# Mainsnode_v2.net
KiCad netlist of a schematic drawn in EAGLE
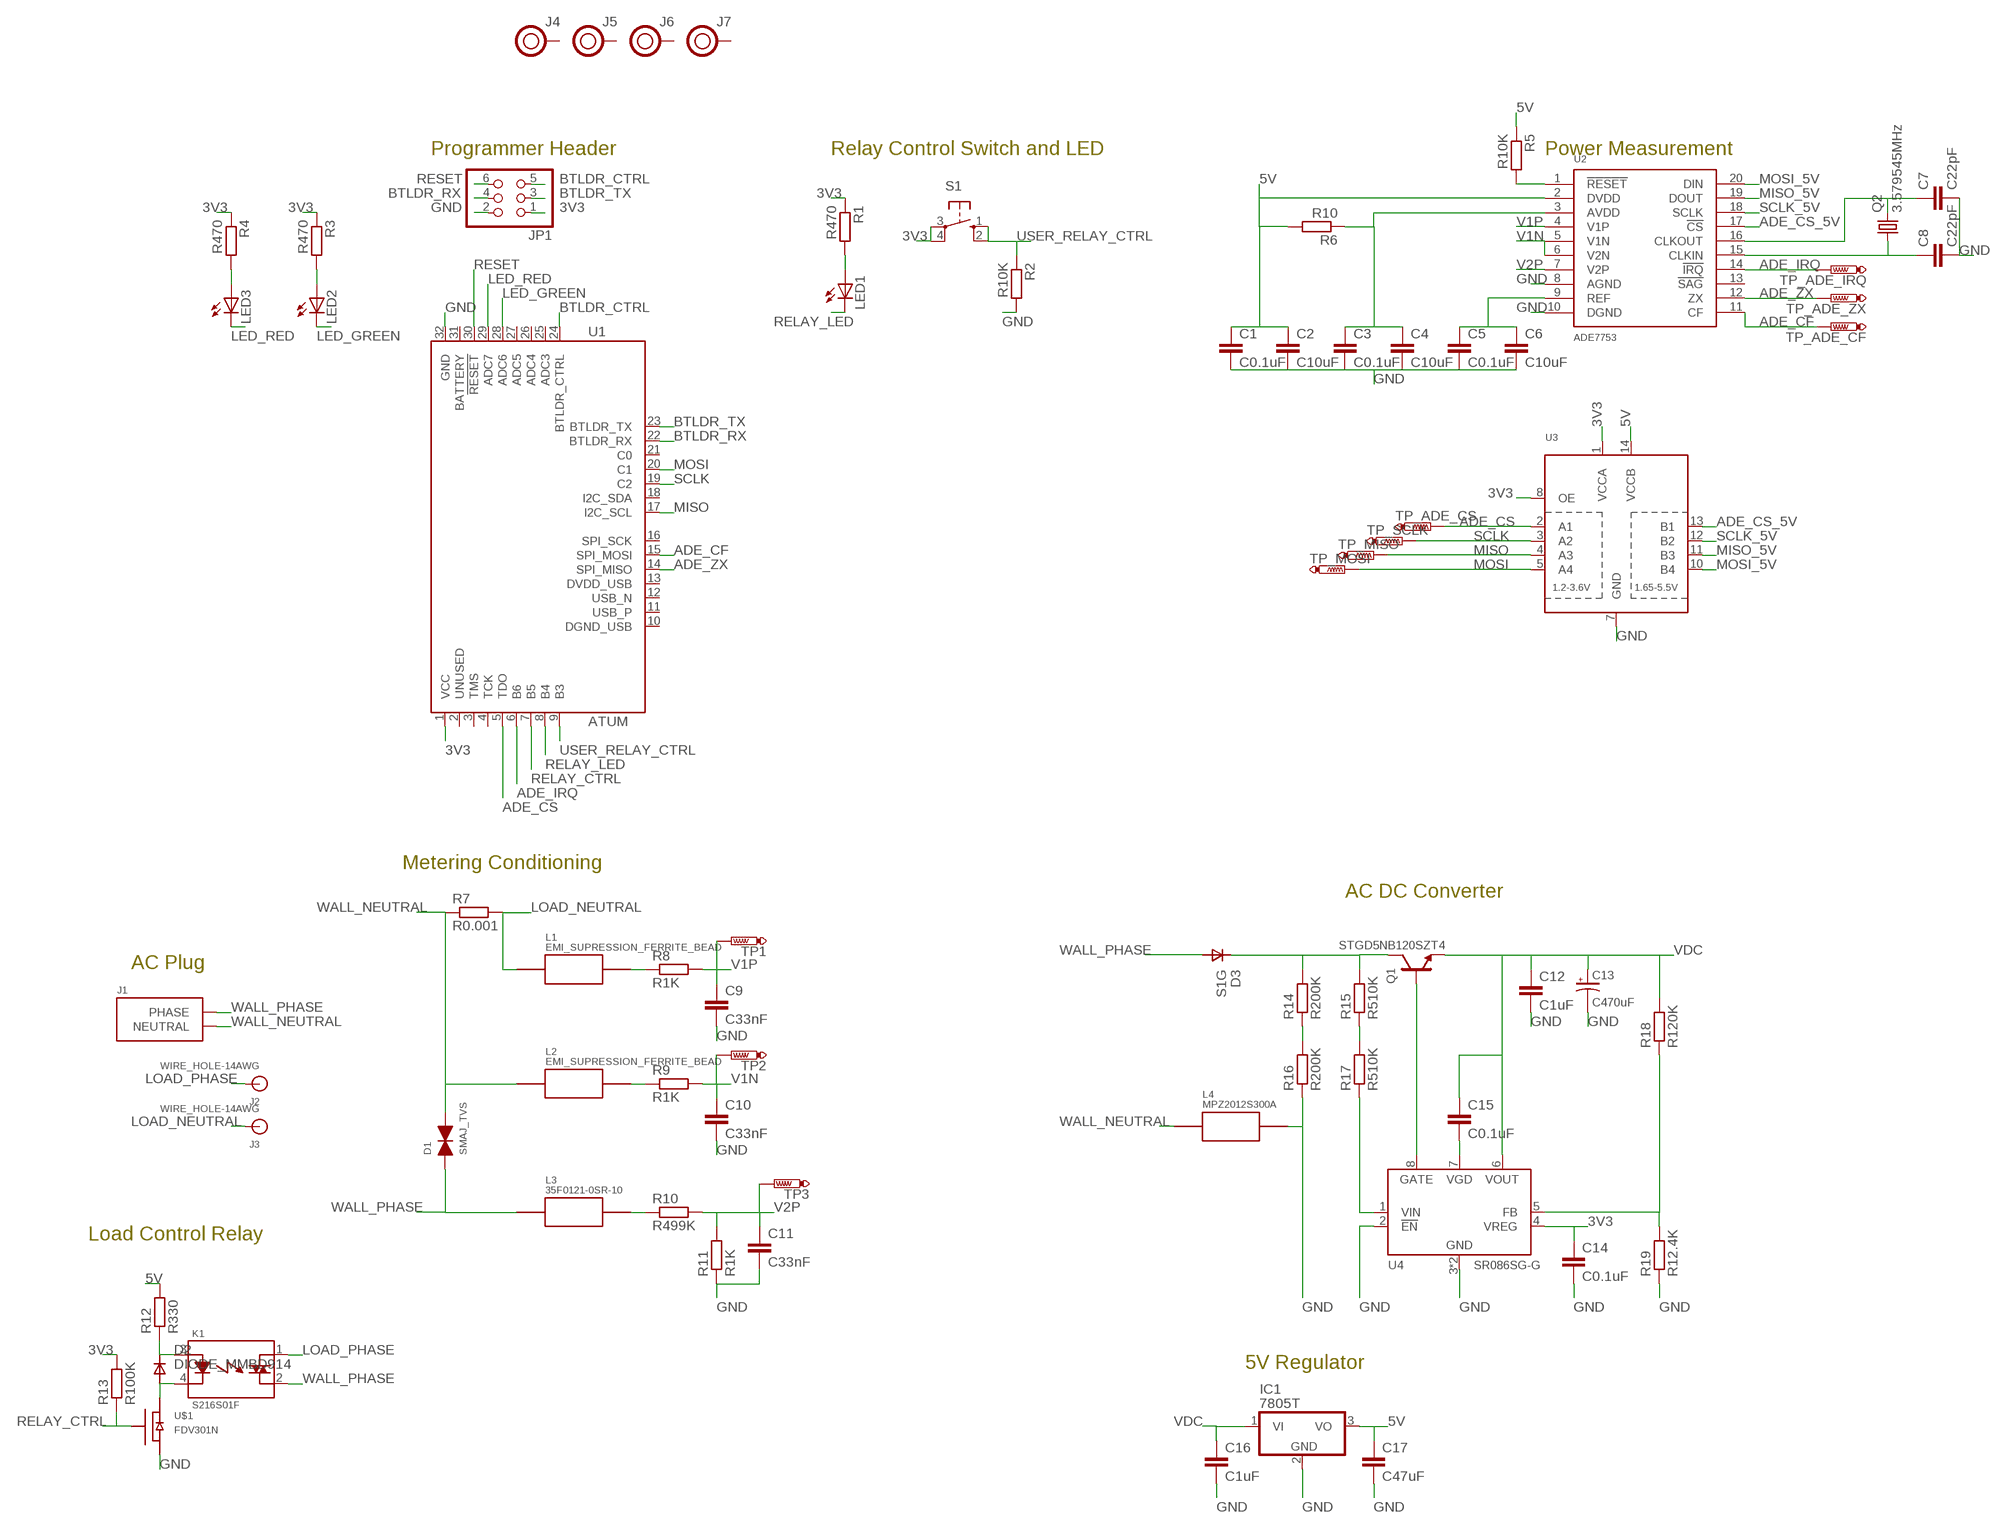
[diagram p0: schematic, sheet 1]

(export (version "E")
  (design (tool "Eeschema 10.0.6"))
  (components
    (comp (ref "C1")
      (value "C0.1uF")
      (footprint "eagle-import:C0805")
      (libsource (lib "eagle-import") (part "C-EUC0805"))
    )
    (comp (ref "C2")
      (value "C10uF")
      (footprint "eagle-import:C0805")
      (libsource (lib "eagle-import") (part "C-EUC0805"))
    )
    (comp (ref "C3")
      (value "C0.1uF")
      (footprint "eagle-import:C0805")
      (libsource (lib "eagle-import") (part "C-EUC0805"))
    )
    (comp (ref "C4")
      (value "C10uF")
      (footprint "eagle-import:C0805")
      (libsource (lib "eagle-import") (part "C-EUC0805"))
    )
    (comp (ref "C5")
      (value "C0.1uF")
      (footprint "eagle-import:C0805")
      (libsource (lib "eagle-import") (part "C-EUC0805"))
    )
    (comp (ref "C6")
      (value "C10uF")
      (footprint "eagle-import:C0805")
      (libsource (lib "eagle-import") (part "C-EUC0805"))
    )
    (comp (ref "C7")
      (value "C22pF")
      (footprint "eagle-import:C0805")
      (libsource (lib "eagle-import") (part "C-EUC0805"))
    )
    (comp (ref "C8")
      (value "C22pF")
      (footprint "eagle-import:C0805")
      (libsource (lib "eagle-import") (part "C-EUC0805"))
    )
    (comp (ref "C9")
      (value "C33nF")
      (footprint "eagle-import:C0805")
      (libsource (lib "eagle-import") (part "C-EUC0805"))
    )
    (comp (ref "C10")
      (value "C33nF")
      (footprint "eagle-import:C0805")
      (libsource (lib "eagle-import") (part "C-EUC0805"))
    )
    (comp (ref "C11")
      (value "C33nF")
      (footprint "eagle-import:C0805")
      (libsource (lib "eagle-import") (part "C-EUC0805"))
    )
    (comp (ref "C12")
      (value "C1uF")
      (footprint "eagle-import:C0805")
      (libsource (lib "eagle-import") (part "C-EUC0805"))
    )
    (comp (ref "C13")
      (value "C470uF")
      (footprint "eagle-import:CAP_SM_10MM")
      (libsource (lib "eagle-import") (part "CAP_EEE-FP1E471AP"))
    )
    (comp (ref "C14")
      (value "C0.1uF")
      (footprint "eagle-import:C0805")
      (libsource (lib "eagle-import") (part "C-EUC0805"))
    )
    (comp (ref "C15")
      (value "C0.1uF")
      (footprint "eagle-import:C0805")
      (libsource (lib "eagle-import") (part "C-EUC0805"))
    )
    (comp (ref "C16")
      (value "C1uF")
      (footprint "eagle-import:C0805")
      (libsource (lib "eagle-import") (part "C-EUC0805"))
    )
    (comp (ref "C17")
      (value "C47uF")
      (footprint "eagle-import:C0805")
      (libsource (lib "eagle-import") (part "C-EUC0805"))
    )
    (comp (ref "D1")
      (value "SMAJ_TVS")
      (footprint "eagle-import:DO214_TVS")
      (libsource (lib "eagle-import") (part "SMAJ_TVS"))
    )
    (comp (ref "D2")
      (value "DIODE_MMBD914")
      (footprint "eagle-import:SOT-23")
      (libsource (lib "eagle-import") (part "DIODE_MMBD914"))
    )
    (comp (ref "D3")
      (value "S1G")
      (footprint "eagle-import:DO-214AC")
      (libsource (lib "eagle-import") (part "S1G"))
    )
    (comp (ref "IC1")
      (value "7805T")
      (footprint "eagle-import:TO220H")
      (libsource (lib "eagle-import") (part "78T05"))
    )
    (comp (ref "J1")
      (value "AC-PLUG-2")
      (footprint "eagle-import:AC_MALE_PINS_2")
      (libsource (lib "eagle-import") (part "AC-PLUG-2"))
    )
    (comp (ref "J2")
      (value "WIRE_HOLE-14AWG")
      (footprint "eagle-import:WIRE_HOLE-14AWG")
      (libsource (lib "eagle-import") (part "WIRE_HOLE-14AWG"))
    )
    (comp (ref "J3")
      (value "WIRE_HOLE-14AWG")
      (footprint "eagle-import:WIRE_HOLE-14AWG")
      (libsource (lib "eagle-import") (part "WIRE_HOLE-14AWG"))
    )
    (comp (ref "J4")
      (value "HOLE")
      (footprint "eagle-import:HOLE-0.125")
      (libsource (lib "eagle-import") (part "HOLE"))
    )
    (comp (ref "J5")
      (value "HOLE")
      (footprint "eagle-import:HOLE-0.125")
      (libsource (lib "eagle-import") (part "HOLE"))
    )
    (comp (ref "J6")
      (value "HOLE")
      (footprint "eagle-import:HOLE-0.125")
      (libsource (lib "eagle-import") (part "HOLE"))
    )
    (comp (ref "J7")
      (value "HOLE")
      (footprint "eagle-import:HOLE-0.125")
      (libsource (lib "eagle-import") (part "HOLE"))
    )
    (comp (ref "JP1")
      (value "PINHD-2X3")
      (footprint "eagle-import:2X03")
      (libsource (lib "eagle-import") (part "PINHD-2X3"))
    )
    (comp (ref "K1")
      (value "S216S01F")
      (footprint "eagle-import:RELAY_SX16S0X")
      (libsource (lib "eagle-import") (part "S216S01F"))
    )
    (comp (ref "L1")
      (value "EMI_SUPRESSION_FERRITE_BEAD")
      (footprint "eagle-import:L1806")
      (libsource (lib "eagle-import") (part "EMI_SUPRESSION_FERRITE_BEAD"))
    )
    (comp (ref "L2")
      (value "EMI_SUPRESSION_FERRITE_BEAD")
      (footprint "eagle-import:L1806")
      (fields (field (name "DIGIKEY") "240-2418-1-ND"))
      (libsource (lib "eagle-import") (part "EMI_SUPRESSION_FERRITE_BEAD"))
    )
    (comp (ref "L3")
      (value "35F0121-0SR-10")
      (footprint "eagle-import:35F0102")
      (libsource (lib "eagle-import") (part "35F0121-0SR-10"))
    )
    (comp (ref "L4")
      (value "MPZ2012S300A")
      (footprint "eagle-import:0805_RESISTOR")
      (libsource (lib "eagle-import") (part "MPZ2012S300A"))
    )
    (comp (ref "LED1")
      (value "LEDCHIP-LED0805")
      (footprint "eagle-import:CHIP-LED0805")
      (libsource (lib "eagle-import") (part "LEDCHIP-LED0805"))
    )
    (comp (ref "LED2")
      (value "LEDCHIP-LED0805")
      (footprint "eagle-import:CHIP-LED0805")
      (libsource (lib "eagle-import") (part "LEDCHIP-LED0805"))
    )
    (comp (ref "LED3")
      (value "LEDCHIP-LED0805")
      (footprint "eagle-import:CHIP-LED0805")
      (libsource (lib "eagle-import") (part "LEDCHIP-LED0805"))
    )
    (comp (ref "Q1")
      (value "STGD5NB120SZT4")
      (footprint "eagle-import:DPAK")
      (libsource (lib "eagle-import") (part "STGD5NB120SZT4"))
    )
    (comp (ref "Q2")
      (value "3.579545MHz")
      (footprint "eagle-import:HC49_S")
      (libsource (lib "eagle-import") (part "CRYSTALHC49S"))
    )
    (comp (ref "R1")
      (value "R470")
      (footprint "eagle-import:R0805")
      (libsource (lib "eagle-import") (part "R-EU_R0805"))
    )
    (comp (ref "R2")
      (value "R10K")
      (footprint "eagle-import:R0805")
      (libsource (lib "eagle-import") (part "R-EU_R0805"))
    )
    (comp (ref "R3")
      (value "R470")
      (footprint "eagle-import:R0805")
      (libsource (lib "eagle-import") (part "R-EU_R0805"))
    )
    (comp (ref "R4")
      (value "R470")
      (footprint "eagle-import:R0805")
      (libsource (lib "eagle-import") (part "R-EU_R0805"))
    )
    (comp (ref "R5")
      (value "R10K")
      (footprint "eagle-import:R0805")
      (libsource (lib "eagle-import") (part "R-EU_R0805"))
    )
    (comp (ref "R6")
      (value "R10")
      (footprint "eagle-import:R0805")
      (libsource (lib "eagle-import") (part "R-EU_R0805"))
    )
    (comp (ref "R7")
      (value "R0.001")
      (footprint "eagle-import:R2512")
      (libsource (lib "eagle-import") (part "R-EU_R2512"))
    )
    (comp (ref "R8")
      (value "R1K")
      (footprint "eagle-import:R0805")
      (libsource (lib "eagle-import") (part "R-EU_R0805"))
    )
    (comp (ref "R9")
      (value "R1K")
      (footprint "eagle-import:R0805")
      (libsource (lib "eagle-import") (part "R-EU_R0805"))
    )
    (comp (ref "R10")
      (value "R499K")
      (footprint "eagle-import:R0805")
      (libsource (lib "eagle-import") (part "R-EU_R0805"))
    )
    (comp (ref "R11")
      (value "R1K")
      (footprint "eagle-import:R0805")
      (libsource (lib "eagle-import") (part "R-EU_R0805"))
    )
    (comp (ref "R12")
      (value "R330")
      (footprint "eagle-import:R0805")
      (libsource (lib "eagle-import") (part "R-EU_R0805"))
    )
    (comp (ref "R13")
      (value "R100K")
      (footprint "eagle-import:R0805")
      (libsource (lib "eagle-import") (part "R-EU_R0805"))
    )
    (comp (ref "R14")
      (value "R200K")
      (footprint "eagle-import:R0805")
      (libsource (lib "eagle-import") (part "R-EU_R0805"))
    )
    (comp (ref "R15")
      (value "R510K")
      (footprint "eagle-import:R0805")
      (libsource (lib "eagle-import") (part "R-EU_R0805"))
    )
    (comp (ref "R16")
      (value "R200K")
      (footprint "eagle-import:R0805")
      (libsource (lib "eagle-import") (part "R-EU_R0805"))
    )
    (comp (ref "R17")
      (value "R510K")
      (footprint "eagle-import:R0805")
      (libsource (lib "eagle-import") (part "R-EU_R0805"))
    )
    (comp (ref "R18")
      (value "R120K")
      (footprint "eagle-import:R0805")
      (libsource (lib "eagle-import") (part "R-EU_R0805"))
    )
    (comp (ref "R19")
      (value "R12.4K")
      (footprint "eagle-import:R0805")
      (libsource (lib "eagle-import") (part "R-EU_R0805"))
    )
    (comp (ref "S1")
      (value "10-XX")
      (footprint "eagle-import:B3F-10XX")
      (fields (field (name "MPN") "B3F-1000"))
      (libsource (lib "eagle-import") (part "10-XX"))
    )
    (comp (ref "TP1")
      (value "PTR1PAD1-13")
      (footprint "eagle-import:P1-13")
      (libsource (lib "eagle-import") (part "PTR1PAD1-13"))
    )
    (comp (ref "TP2")
      (value "PTR1PAD1-13")
      (footprint "eagle-import:P1-13")
      (libsource (lib "eagle-import") (part "PTR1PAD1-13"))
    )
    (comp (ref "TP3")
      (value "PTR1PAD1-13")
      (footprint "eagle-import:P1-13")
      (libsource (lib "eagle-import") (part "PTR1PAD1-13"))
    )
    (comp (ref "TP_ADE_CF")
      (value "PTR1PAD1-13")
      (footprint "eagle-import:P1-13")
      (libsource (lib "eagle-import") (part "PTR1PAD1-13"))
    )
    (comp (ref "TP_ADE_CS")
      (value "PTR1PAD1-13")
      (footprint "eagle-import:P1-13")
      (libsource (lib "eagle-import") (part "PTR1PAD1-13"))
    )
    (comp (ref "TP_ADE_IRQ")
      (value "PTR1PAD1-13")
      (footprint "eagle-import:P1-13")
      (libsource (lib "eagle-import") (part "PTR1PAD1-13"))
    )
    (comp (ref "TP_ADE_ZX")
      (value "PTR1PAD1-13")
      (footprint "eagle-import:P1-13")
      (libsource (lib "eagle-import") (part "PTR1PAD1-13"))
    )
    (comp (ref "TP_MISO")
      (value "PTR1PAD1-13")
      (footprint "eagle-import:P1-13")
      (libsource (lib "eagle-import") (part "PTR1PAD1-13"))
    )
    (comp (ref "TP_MOSI")
      (value "PTR1PAD1-13")
      (footprint "eagle-import:P1-13")
      (libsource (lib "eagle-import") (part "PTR1PAD1-13"))
    )
    (comp (ref "TP_SCLK")
      (value "PTR1PAD1-13")
      (footprint "eagle-import:P1-13")
      (libsource (lib "eagle-import") (part "PTR1PAD1-13"))
    )
    (comp (ref "U$1")
      (value "FDV301N")
      (footprint "eagle-import:SOT-23")
      (libsource (lib "eagle-import") (part "FDV301N"))
    )
    (comp (ref "U1")
      (value "ATUM")
      (footprint "eagle-import:ATUM")
      (libsource (lib "eagle-import") (part "ATUM"))
    )
    (comp (ref "U2")
      (value "ADE7753")
      (footprint "eagle-import:SSOP-20")
      (libsource (lib "eagle-import") (part "ADE7753"))
    )
    (comp (ref "U3")
      (value "TXB0104PWR")
      (footprint "eagle-import:TSSOP14")
      (libsource (lib "eagle-import") (part "TXB0104PWR"))
    )
    (comp (ref "U4")
      (value "SR086SG-G")
      (footprint "eagle-import:SR086")
      (libsource (lib "eagle-import") (part "SR086SG-G"))
    )
  )
  (nets
    (net (code "1") (name "/3V3") (class "Default")
      (node (ref "C14") (pin "1") (pinfunction "1_1") (pintype "passive"))
      (node (ref "JP1") (pin "1") (pinfunction "1_1") (pintype "passive"))
      (node (ref "R1") (pin "1") (pinfunction "1_1") (pintype "passive"))
      (node (ref "R13") (pin "2") (pinfunction "2_2") (pintype "passive"))
      (node (ref "R3") (pin "1") (pinfunction "1_1") (pintype "passive"))
      (node (ref "R4") (pin "1") (pinfunction "1_1") (pintype "passive"))
      (node (ref "S1") (pin "3") (pinfunction "P_3") (pintype "passive"))
      (node (ref "S1") (pin "4") (pinfunction "P1_4") (pintype "passive"))
      (node (ref "U1") (pin "1") (pinfunction "VCC_1") (pintype "bidirectional"))
      (node (ref "U3") (pin "1") (pinfunction "VCCA_1") (pintype "bidirectional"))
      (node (ref "U3") (pin "8") (pinfunction "OE_8") (pintype "bidirectional"))
      (node (ref "U4") (pin "4") (pinfunction "VREG_4") (pintype "bidirectional"))
    )
    (net (code "2") (name "/5V") (class "Default")
      (node (ref "C1") (pin "1") (pinfunction "1_1") (pintype "passive"))
      (node (ref "C17") (pin "1") (pinfunction "1_1") (pintype "passive"))
      (node (ref "C2") (pin "1") (pinfunction "1_1") (pintype "passive"))
      (node (ref "IC1") (pin "3") (pinfunction "VO_3") (pintype "passive"))
      (node (ref "R12") (pin "2") (pinfunction "2_2") (pintype "passive"))
      (node (ref "R5") (pin "1") (pinfunction "1_1") (pintype "passive"))
      (node (ref "R6") (pin "2") (pinfunction "2_2") (pintype "passive"))
      (node (ref "U2") (pin "2") (pinfunction "DVDD_2") (pintype "bidirectional"))
      (node (ref "U3") (pin "14") (pinfunction "VCCB_14") (pintype "bidirectional"))
    )
    (net (code "3") (name "/ADE_CF") (class "Default")
      (node (ref "TP_ADE_CF") (pin "TP") (pinfunction "TP_TP") (pintype "input"))
      (node (ref "U1") (pin "15") (pinfunction "SPI_MOSI_15") (pintype "bidirectional"))
      (node (ref "U2") (pin "11") (pinfunction "CF_11") (pintype "bidirectional"))
    )
    (net (code "4") (name "/ADE_CS") (class "Default")
      (node (ref "TP_ADE_CS") (pin "TP") (pinfunction "TP_TP") (pintype "input"))
      (node (ref "U1") (pin "5") (pinfunction "TDO_5") (pintype "bidirectional"))
      (node (ref "U3") (pin "2") (pinfunction "A1_2") (pintype "bidirectional"))
    )
    (net (code "5") (name "/ADE_CS_5V") (class "Default")
      (node (ref "U2") (pin "17") (pinfunction "~{CS}_17") (pintype "bidirectional"))
      (node (ref "U3") (pin "13") (pinfunction "B1_13") (pintype "bidirectional"))
    )
    (net (code "6") (name "/ADE_IRQ") (class "Default")
      (node (ref "TP_ADE_IRQ") (pin "TP") (pinfunction "TP_TP") (pintype "input"))
      (node (ref "U1") (pin "6") (pinfunction "B6_6") (pintype "bidirectional"))
      (node (ref "U2") (pin "14") (pinfunction "~{IRQ}_14") (pintype "bidirectional"))
    )
    (net (code "7") (name "/ADE_ZX") (class "Default")
      (node (ref "TP_ADE_ZX") (pin "TP") (pinfunction "TP_TP") (pintype "input"))
      (node (ref "U1") (pin "14") (pinfunction "SPI_MISO_14") (pintype "bidirectional"))
      (node (ref "U2") (pin "12") (pinfunction "ZX_12") (pintype "bidirectional"))
    )
    (net (code "8") (name "/BTLDR_CTRL") (class "Default")
      (node (ref "JP1") (pin "5") (pinfunction "5_5") (pintype "passive"))
      (node (ref "U1") (pin "24") (pinfunction "BTLDR_CTRL_24") (pintype "bidirectional"))
    )
    (net (code "9") (name "/BTLDR_RX") (class "Default")
      (node (ref "JP1") (pin "4") (pinfunction "4_4") (pintype "passive"))
      (node (ref "U1") (pin "22") (pinfunction "BTLDR_RX_22") (pintype "bidirectional"))
    )
    (net (code "10") (name "/BTLDR_TX") (class "Default")
      (node (ref "JP1") (pin "3") (pinfunction "3_3") (pintype "passive"))
      (node (ref "U1") (pin "23") (pinfunction "BTLDR_TX_23") (pintype "bidirectional"))
    )
    (net (code "11") (name "/GND") (class "Default")
      (node (ref "C1") (pin "2") (pinfunction "2_2") (pintype "passive"))
      (node (ref "C10") (pin "2") (pinfunction "2_2") (pintype "passive"))
      (node (ref "C11") (pin "2") (pinfunction "2_2") (pintype "passive"))
      (node (ref "C12") (pin "2") (pinfunction "2_2") (pintype "passive"))
      (node (ref "C13") (pin "-") (pinfunction "-_-") (pintype "bidirectional"))
      (node (ref "C14") (pin "2") (pinfunction "2_2") (pintype "passive"))
      (node (ref "C16") (pin "2") (pinfunction "2_2") (pintype "passive"))
      (node (ref "C17") (pin "2") (pinfunction "2_2") (pintype "passive"))
      (node (ref "C2") (pin "2") (pinfunction "2_2") (pintype "passive"))
      (node (ref "C3") (pin "2") (pinfunction "2_2") (pintype "passive"))
      (node (ref "C4") (pin "2") (pinfunction "2_2") (pintype "passive"))
      (node (ref "C5") (pin "2") (pinfunction "2_2") (pintype "passive"))
      (node (ref "C6") (pin "2") (pinfunction "2_2") (pintype "passive"))
      (node (ref "C7") (pin "2") (pinfunction "2_2") (pintype "passive"))
      (node (ref "C8") (pin "2") (pinfunction "2_2") (pintype "passive"))
      (node (ref "C9") (pin "2") (pinfunction "2_2") (pintype "passive"))
      (node (ref "IC1") (pin "2") (pinfunction "GND_2") (pintype "passive"))
      (node (ref "JP1") (pin "2") (pinfunction "2_2") (pintype "passive"))
      (node (ref "L4") (pin "P$2") (pinfunction "P$2_P$2") (pintype "bidirectional"))
      (node (ref "R11") (pin "1") (pinfunction "1_1") (pintype "passive"))
      (node (ref "R16") (pin "1") (pinfunction "1_1") (pintype "passive"))
      (node (ref "R19") (pin "1") (pinfunction "1_1") (pintype "passive"))
      (node (ref "R2") (pin "2") (pinfunction "2_2") (pintype "passive"))
      (node (ref "U$1") (pin "2") (pinfunction "S_2") (pintype "bidirectional"))
      (node (ref "U1") (pin "32") (pinfunction "GND_32") (pintype "bidirectional"))
      (node (ref "U2") (pin "10") (pinfunction "DGND_10") (pintype "bidirectional"))
      (node (ref "U2") (pin "8") (pinfunction "AGND_8") (pintype "bidirectional"))
      (node (ref "U3") (pin "7") (pinfunction "GND_7") (pintype "bidirectional"))
      (node (ref "U4") (pin "2") (pinfunction "~{EN}_2") (pintype "bidirectional"))
      (node (ref "U4") (pin "3") (pinfunction "GND_3") (pintype "bidirectional"))
      (node (ref "U4") (pin "PAD") (pinfunction "GND_PAD") (pintype "bidirectional"))
    )
    (net (code "12") (name "/LED_GREEN") (class "Default")
      (node (ref "LED2") (pin "C") (pinfunction "C_C") (pintype "passive"))
      (node (ref "U1") (pin "28") (pinfunction "ADC6_28") (pintype "bidirectional"))
    )
    (net (code "13") (name "/LED_RED") (class "Default")
      (node (ref "LED3") (pin "C") (pinfunction "C_C") (pintype "passive"))
      (node (ref "U1") (pin "29") (pinfunction "ADC7_29") (pintype "bidirectional"))
    )
    (net (code "14") (name "/LOAD_NEUTRAL") (class "Default")
      (node (ref "J3") (pin "P$1") (pinfunction "P$1_P$1") (pintype "bidirectional"))
      (node (ref "L1") (pin "P$1") (pinfunction "P$1_P$1") (pintype "bidirectional"))
      (node (ref "R7") (pin "2") (pinfunction "2_2") (pintype "passive"))
    )
    (net (code "15") (name "/LOAD_PHASE") (class "Default")
      (node (ref "J2") (pin "P$1") (pinfunction "P$1_P$1") (pintype "bidirectional"))
      (node (ref "K1") (pin "1") (pinfunction "1_1") (pintype "bidirectional"))
    )
    (net (code "16") (name "/MISO") (class "Default")
      (node (ref "TP_MISO") (pin "TP") (pinfunction "TP_TP") (pintype "input"))
      (node (ref "U1") (pin "17") (pinfunction "I2C_SCL_17") (pintype "bidirectional"))
      (node (ref "U3") (pin "4") (pinfunction "A3_4") (pintype "bidirectional"))
    )
    (net (code "17") (name "/MISO_5V") (class "Default")
      (node (ref "U2") (pin "19") (pinfunction "DOUT_19") (pintype "bidirectional"))
      (node (ref "U3") (pin "11") (pinfunction "B3_11") (pintype "bidirectional"))
    )
    (net (code "18") (name "/MOSI") (class "Default")
      (node (ref "TP_MOSI") (pin "TP") (pinfunction "TP_TP") (pintype "input"))
      (node (ref "U1") (pin "20") (pinfunction "C1_20") (pintype "bidirectional"))
      (node (ref "U3") (pin "5") (pinfunction "A4_5") (pintype "bidirectional"))
    )
    (net (code "19") (name "/MOSI_5V") (class "Default")
      (node (ref "U2") (pin "20") (pinfunction "DIN_20") (pintype "bidirectional"))
      (node (ref "U3") (pin "10") (pinfunction "B4_10") (pintype "bidirectional"))
    )
    (net (code "20") (name "/RELAY_CTRL") (class "Default")
      (node (ref "R13") (pin "1") (pinfunction "1_1") (pintype "passive"))
      (node (ref "U$1") (pin "1") (pinfunction "G_1") (pintype "bidirectional"))
      (node (ref "U1") (pin "7") (pinfunction "B5_7") (pintype "bidirectional"))
    )
    (net (code "21") (name "/RELAY_LED") (class "Default")
      (node (ref "LED1") (pin "C") (pinfunction "C_C") (pintype "passive"))
      (node (ref "U1") (pin "8") (pinfunction "B4_8") (pintype "bidirectional"))
    )
    (net (code "22") (name "/RESET") (class "Default")
      (node (ref "JP1") (pin "6") (pinfunction "6_6") (pintype "passive"))
      (node (ref "U1") (pin "30") (pinfunction "~{RESET}_30") (pintype "bidirectional"))
    )
    (net (code "23") (name "/SCLK") (class "Default")
      (node (ref "TP_SCLK") (pin "TP") (pinfunction "TP_TP") (pintype "input"))
      (node (ref "U1") (pin "19") (pinfunction "C2_19") (pintype "bidirectional"))
      (node (ref "U3") (pin "3") (pinfunction "A2_3") (pintype "bidirectional"))
    )
    (net (code "24") (name "/SCLK_5V") (class "Default")
      (node (ref "U2") (pin "18") (pinfunction "SCLK_18") (pintype "bidirectional"))
      (node (ref "U3") (pin "12") (pinfunction "B2_12") (pintype "bidirectional"))
    )
    (net (code "25") (name "/USER_RELAY_CTRL") (class "Default")
      (node (ref "R2") (pin "1") (pinfunction "1_1") (pintype "passive"))
      (node (ref "S1") (pin "1") (pinfunction "S_1") (pintype "passive"))
      (node (ref "S1") (pin "2") (pinfunction "S1_2") (pintype "passive"))
      (node (ref "U1") (pin "9") (pinfunction "B3_9") (pintype "bidirectional"))
    )
    (net (code "26") (name "/V1N") (class "Default")
      (node (ref "C10") (pin "1") (pinfunction "1_1") (pintype "passive"))
      (node (ref "R9") (pin "2") (pinfunction "2_2") (pintype "passive"))
      (node (ref "TP2") (pin "TP") (pinfunction "TP_TP") (pintype "input"))
      (node (ref "U2") (pin "5") (pinfunction "V1N_5") (pintype "bidirectional"))
      (node (ref "U2") (pin "6") (pinfunction "V2N_6") (pintype "bidirectional"))
    )
    (net (code "27") (name "/V1P") (class "Default")
      (node (ref "C9") (pin "1") (pinfunction "1_1") (pintype "passive"))
      (node (ref "R8") (pin "2") (pinfunction "2_2") (pintype "passive"))
      (node (ref "TP1") (pin "TP") (pinfunction "TP_TP") (pintype "input"))
      (node (ref "U2") (pin "4") (pinfunction "V1P_4") (pintype "bidirectional"))
    )
    (net (code "28") (name "/V2P") (class "Default")
      (node (ref "C11") (pin "1") (pinfunction "1_1") (pintype "passive"))
      (node (ref "R10") (pin "2") (pinfunction "2_2") (pintype "passive"))
      (node (ref "R11") (pin "2") (pinfunction "2_2") (pintype "passive"))
      (node (ref "TP3") (pin "TP") (pinfunction "TP_TP") (pintype "input"))
      (node (ref "U2") (pin "7") (pinfunction "V2P_7") (pintype "bidirectional"))
    )
    (net (code "29") (name "/VDC") (class "Default")
      (node (ref "C12") (pin "1") (pinfunction "1_1") (pintype "passive"))
      (node (ref "C13") (pin "+") (pinfunction "+_+") (pintype "bidirectional"))
      (node (ref "C15") (pin "1") (pinfunction "1_1") (pintype "passive"))
      (node (ref "C16") (pin "1") (pinfunction "1_1") (pintype "passive"))
      (node (ref "IC1") (pin "1") (pinfunction "VI_1") (pintype "input"))
      (node (ref "Q1") (pin "P$3") (pinfunction "E_P$3") (pintype "bidirectional"))
      (node (ref "R18") (pin "2") (pinfunction "2_2") (pintype "passive"))
      (node (ref "U4") (pin "6") (pinfunction "VOUT_6") (pintype "bidirectional"))
    )
    (net (code "30") (name "/WALL_NEUTRAL") (class "Default")
      (node (ref "D1") (pin "CATHODE") (pinfunction "P$2_CATHODE") (pintype "bidirectional"))
      (node (ref "J1") (pin "NEUTRAL1") (pinfunction "NEUTRAL_NEUTRAL1") (pintype "bidirectional"))
      (node (ref "J1") (pin "NEUTRAL2") (pinfunction "NEUTRAL_NEUTRAL2") (pintype "bidirectional"))
      (node (ref "L2") (pin "P$1") (pinfunction "P$1_P$1") (pintype "bidirectional"))
      (node (ref "L4") (pin "P$1") (pinfunction "P$1_P$1") (pintype "bidirectional"))
      (node (ref "R7") (pin "1") (pinfunction "1_1") (pintype "passive"))
    )
    (net (code "31") (name "/WALL_PHASE") (class "Default")
      (node (ref "D1") (pin "ANODE") (pinfunction "P$1_ANODE") (pintype "bidirectional"))
      (node (ref "D3") (pin "ANNODE") (pinfunction "ANNODE_ANNODE") (pintype "bidirectional"))
      (node (ref "J1") (pin "PHASE1") (pinfunction "PHASE_PHASE1") (pintype "bidirectional"))
      (node (ref "J1") (pin "PHASE2") (pinfunction "PHASE_PHASE2") (pintype "bidirectional"))
      (node (ref "K1") (pin "2") (pinfunction "2_2") (pintype "bidirectional"))
      (node (ref "L3") (pin "1") (pinfunction "P$1_1") (pintype "bidirectional"))
    )
    (net (code "32") (name "Net-(D2-ANNODE)") (class "Default")
      (node (ref "D2") (pin "1") (pinfunction "ANNODE_1") (pintype "bidirectional"))
      (node (ref "K1") (pin "4") (pinfunction "4_4") (pintype "bidirectional"))
      (node (ref "U$1") (pin "3") (pinfunction "D_3") (pintype "bidirectional"))
    )
    (net (code "33") (name "Net-(D2-CATHODE)") (class "Default")
      (node (ref "D2") (pin "3") (pinfunction "CATHODE_3") (pintype "bidirectional"))
      (node (ref "K1") (pin "3") (pinfunction "3_3") (pintype "bidirectional"))
      (node (ref "R12") (pin "1") (pinfunction "1_1") (pintype "passive"))
    )
    (net (code "34") (name "Net-(L1-PadP$2)") (class "Default")
      (node (ref "L1") (pin "P$2") (pinfunction "P$2_P$2") (pintype "bidirectional"))
      (node (ref "R8") (pin "1") (pinfunction "1_1") (pintype "passive"))
    )
    (net (code "35") (name "Net-(L2-PadP$2)") (class "Default")
      (node (ref "L2") (pin "P$2") (pinfunction "P$2_P$2") (pintype "bidirectional"))
      (node (ref "R9") (pin "1") (pinfunction "1_1") (pintype "passive"))
    )
    (net (code "36") (name "Net-(L3-P$2)") (class "Default")
      (node (ref "L3") (pin "2") (pinfunction "P$2_2") (pintype "bidirectional"))
      (node (ref "R10") (pin "1") (pinfunction "1_1") (pintype "passive"))
    )
    (net (code "37") (name "Net-(LED1-PadA)") (class "Default")
      (node (ref "LED1") (pin "A") (pinfunction "A_A") (pintype "passive"))
      (node (ref "R1") (pin "2") (pinfunction "2_2") (pintype "passive"))
    )
    (net (code "38") (name "Net-(LED2-PadA)") (class "Default")
      (node (ref "LED2") (pin "A") (pinfunction "A_A") (pintype "passive"))
      (node (ref "R3") (pin "2") (pinfunction "2_2") (pintype "passive"))
    )
    (net (code "39") (name "Net-(LED3-PadA)") (class "Default")
      (node (ref "LED3") (pin "A") (pinfunction "A_A") (pintype "passive"))
      (node (ref "R4") (pin "2") (pinfunction "2_2") (pintype "passive"))
    )
    (net (code "40") (name "Net-(Q1-C)") (class "Default")
      (node (ref "D3") (pin "CATHODE") (pinfunction "CATHODE_CATHODE") (pintype "bidirectional"))
      (node (ref "Q1") (pin "P$2") (pinfunction "C_P$2") (pintype "bidirectional"))
      (node (ref "R14") (pin "2") (pinfunction "2_2") (pintype "passive"))
      (node (ref "R15") (pin "2") (pinfunction "2_2") (pintype "passive"))
    )
    (net (code "41") (name "Net-(Q1-G)") (class "Default")
      (node (ref "Q1") (pin "P$1") (pinfunction "G_P$1") (pintype "bidirectional"))
      (node (ref "U4") (pin "8") (pinfunction "GATE_8") (pintype "bidirectional"))
    )
    (net (code "42") (name "Net-(R14-Pad1)") (class "Default")
      (node (ref "R14") (pin "1") (pinfunction "1_1") (pintype "passive"))
      (node (ref "R16") (pin "2") (pinfunction "2_2") (pintype "passive"))
    )
    (net (code "43") (name "Net-(R15-Pad1)") (class "Default")
      (node (ref "R15") (pin "1") (pinfunction "1_1") (pintype "passive"))
      (node (ref "R17") (pin "2") (pinfunction "2_2") (pintype "passive"))
    )
    (net (code "44") (name "Net-(U2-AVDD)") (class "Default")
      (node (ref "C3") (pin "1") (pinfunction "1_1") (pintype "passive"))
      (node (ref "C4") (pin "1") (pinfunction "1_1") (pintype "passive"))
      (node (ref "R6") (pin "1") (pinfunction "1_1") (pintype "passive"))
      (node (ref "U2") (pin "3") (pinfunction "AVDD_3") (pintype "bidirectional"))
    )
    (net (code "45") (name "Net-(U2-CLKIN)") (class "Default")
      (node (ref "C8") (pin "1") (pinfunction "1_1") (pintype "passive"))
      (node (ref "Q2") (pin "1") (pinfunction "1_1") (pintype "passive"))
      (node (ref "U2") (pin "15") (pinfunction "CLKIN_15") (pintype "bidirectional"))
    )
    (net (code "46") (name "Net-(U2-CLKOUT)") (class "Default")
      (node (ref "C7") (pin "1") (pinfunction "1_1") (pintype "passive"))
      (node (ref "Q2") (pin "2") (pinfunction "2_2") (pintype "passive"))
      (node (ref "U2") (pin "16") (pinfunction "CLKOUT_16") (pintype "bidirectional"))
    )
    (net (code "47") (name "Net-(U2-REF)") (class "Default")
      (node (ref "C5") (pin "1") (pinfunction "1_1") (pintype "passive"))
      (node (ref "C6") (pin "1") (pinfunction "1_1") (pintype "passive"))
      (node (ref "U2") (pin "9") (pinfunction "REF_9") (pintype "bidirectional"))
    )
    (net (code "48") (name "Net-(U2-~{RESET})") (class "Default")
      (node (ref "R5") (pin "2") (pinfunction "2_2") (pintype "passive"))
      (node (ref "U2") (pin "1") (pinfunction "~{RESET}_1") (pintype "bidirectional"))
    )
    (net (code "49") (name "Net-(U4-FB)") (class "Default")
      (node (ref "R18") (pin "1") (pinfunction "1_1") (pintype "passive"))
      (node (ref "R19") (pin "2") (pinfunction "2_2") (pintype "passive"))
      (node (ref "U4") (pin "5") (pinfunction "FB_5") (pintype "bidirectional"))
    )
    (net (code "50") (name "Net-(U4-VGD)") (class "Default")
      (node (ref "C15") (pin "2") (pinfunction "2_2") (pintype "passive"))
      (node (ref "U4") (pin "7") (pinfunction "VGD_7") (pintype "bidirectional"))
    )
    (net (code "51") (name "Net-(U4-VIN)") (class "Default")
      (node (ref "R17") (pin "1") (pinfunction "1_1") (pintype "passive"))
      (node (ref "U4") (pin "1") (pinfunction "VIN_1") (pintype "bidirectional"))
    )
    (net (code "52") (name "unconnected-(J4-P$1-Pad1)") (class "Default")
      (node (ref "J4") (pin "1") (pinfunction "P$1_1") (pintype "bidirectional"))
    )
    (net (code "53") (name "unconnected-(J5-P$1-Pad1)") (class "Default")
      (node (ref "J5") (pin "1") (pinfunction "P$1_1") (pintype "bidirectional"))
    )
    (net (code "54") (name "unconnected-(J6-P$1-Pad1)") (class "Default")
      (node (ref "J6") (pin "1") (pinfunction "P$1_1") (pintype "bidirectional"))
    )
    (net (code "55") (name "unconnected-(J7-P$1-Pad1)") (class "Default")
      (node (ref "J7") (pin "1") (pinfunction "P$1_1") (pintype "bidirectional"))
    )
    (net (code "56") (name "unconnected-(U1-ADC3-Pad25)") (class "Default")
      (node (ref "U1") (pin "25") (pinfunction "ADC3_25") (pintype "bidirectional"))
    )
    (net (code "57") (name "unconnected-(U1-ADC4-Pad26)") (class "Default")
      (node (ref "U1") (pin "26") (pinfunction "ADC4_26") (pintype "bidirectional"))
    )
    (net (code "58") (name "unconnected-(U1-ADC5-Pad27)") (class "Default")
      (node (ref "U1") (pin "27") (pinfunction "ADC5_27") (pintype "bidirectional"))
    )
    (net (code "59") (name "unconnected-(U1-BATTERY-Pad31)") (class "Default")
      (node (ref "U1") (pin "31") (pinfunction "BATTERY_31") (pintype "bidirectional"))
    )
    (net (code "60") (name "unconnected-(U1-C0-Pad21)") (class "Default")
      (node (ref "U1") (pin "21") (pinfunction "C0_21") (pintype "bidirectional"))
    )
    (net (code "61") (name "unconnected-(U1-DGND_USB-Pad10)") (class "Default")
      (node (ref "U1") (pin "10") (pinfunction "DGND_USB_10") (pintype "bidirectional"))
    )
    (net (code "62") (name "unconnected-(U1-DVDD_USB-Pad13)") (class "Default")
      (node (ref "U1") (pin "13") (pinfunction "DVDD_USB_13") (pintype "bidirectional"))
    )
    (net (code "63") (name "unconnected-(U1-I2C_SDA-Pad18)") (class "Default")
      (node (ref "U1") (pin "18") (pinfunction "I2C_SDA_18") (pintype "bidirectional"))
    )
    (net (code "64") (name "unconnected-(U1-SPI_SCK-Pad16)") (class "Default")
      (node (ref "U1") (pin "16") (pinfunction "SPI_SCK_16") (pintype "bidirectional"))
    )
    (net (code "65") (name "unconnected-(U1-TCK-Pad4)") (class "Default")
      (node (ref "U1") (pin "4") (pinfunction "TCK_4") (pintype "bidirectional"))
    )
    (net (code "66") (name "unconnected-(U1-TMS-Pad3)") (class "Default")
      (node (ref "U1") (pin "3") (pinfunction "TMS_3") (pintype "bidirectional"))
    )
    (net (code "67") (name "unconnected-(U1-UNUSED-Pad2)") (class "Default")
      (node (ref "U1") (pin "2") (pinfunction "UNUSED_2") (pintype "bidirectional"))
    )
    (net (code "68") (name "unconnected-(U1-USB_N-Pad12)") (class "Default")
      (node (ref "U1") (pin "12") (pinfunction "USB_N_12") (pintype "bidirectional"))
    )
    (net (code "69") (name "unconnected-(U1-USB_P-Pad11)") (class "Default")
      (node (ref "U1") (pin "11") (pinfunction "USB_P_11") (pintype "bidirectional"))
    )
    (net (code "70") (name "unconnected-(U2-~{SAG}-Pad13)") (class "Default")
      (node (ref "U2") (pin "13") (pinfunction "~{SAG}_13") (pintype "bidirectional"))
    )
  )
)
